# gl827.net
KiCad netlist of a schematic drawn in EAGLE
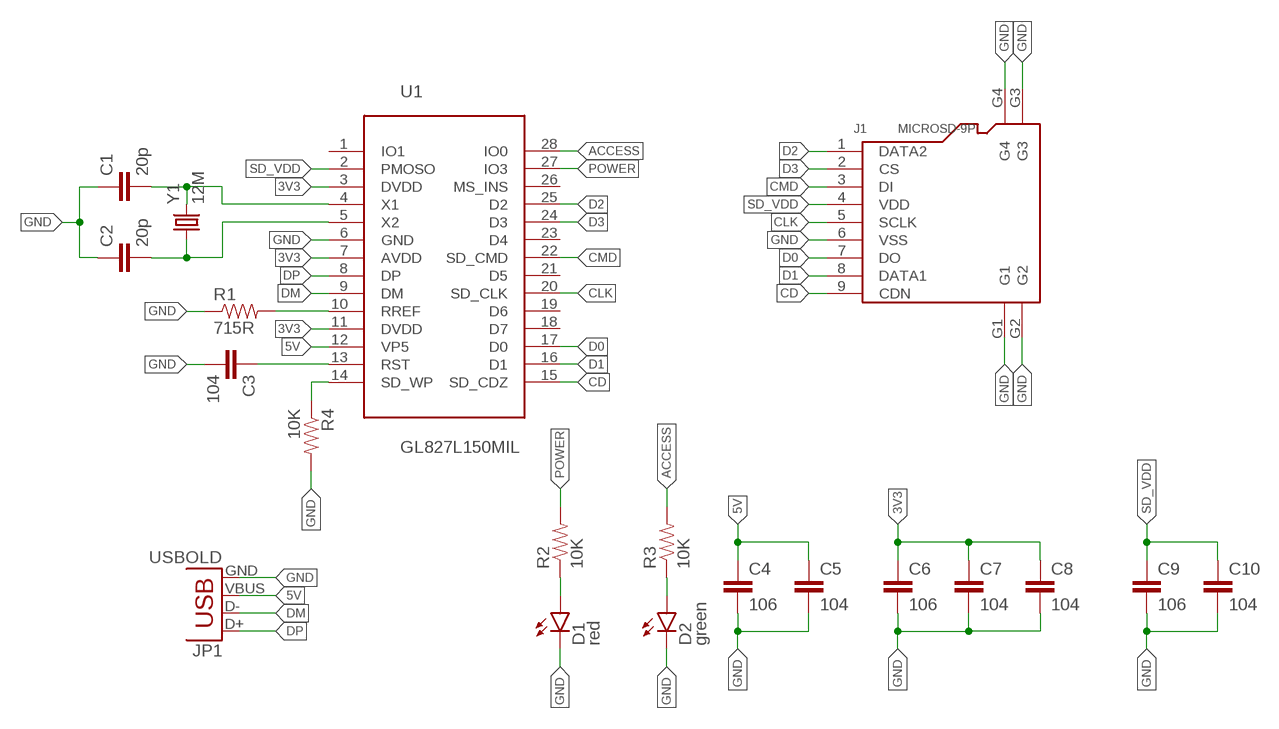
[diagram p0: schematic, sheet 1]

(export (version "E")
  (design (tool "Eeschema 10.0.6"))
  (components
    (comp (ref "C1")
      (value "20p")
      (footprint "eagle-import:0402-CAP")
      (libsource (lib "eagle-import") (part "CAP0402-CAP"))
    )
    (comp (ref "C2")
      (value "20p")
      (footprint "eagle-import:0402-CAP")
      (libsource (lib "eagle-import") (part "CAP0402-CAP"))
    )
    (comp (ref "C3")
      (value "104")
      (footprint "eagle-import:0402-CAP")
      (libsource (lib "eagle-import") (part "CAP0402-CAP"))
    )
    (comp (ref "C4")
      (value "106")
      (footprint "eagle-import:0402-CAP")
      (libsource (lib "eagle-import") (part "CAP0402-CAP"))
    )
    (comp (ref "C5")
      (value "104")
      (footprint "eagle-import:0402-CAP")
      (libsource (lib "eagle-import") (part "CAP0402-CAP"))
    )
    (comp (ref "C6")
      (value "106")
      (footprint "eagle-import:0402-CAP")
      (libsource (lib "eagle-import") (part "CAP0402-CAP"))
    )
    (comp (ref "C7")
      (value "104")
      (footprint "eagle-import:0402-CAP")
      (libsource (lib "eagle-import") (part "CAP0402-CAP"))
    )
    (comp (ref "C8")
      (value "104")
      (footprint "eagle-import:0402-CAP")
      (libsource (lib "eagle-import") (part "CAP0402-CAP"))
    )
    (comp (ref "C9")
      (value "106")
      (footprint "eagle-import:0402-CAP")
      (libsource (lib "eagle-import") (part "CAP0402-CAP"))
    )
    (comp (ref "C10")
      (value "104")
      (footprint "eagle-import:0402-CAP")
      (libsource (lib "eagle-import") (part "CAP0402-CAP"))
    )
    (comp (ref "D1")
      (value "red")
      (footprint "eagle-import:LED-0603-EASY")
      (libsource (lib "eagle-import") (part "LED-EASY"))
    )
    (comp (ref "D2")
      (value "green")
      (footprint "eagle-import:LED-0603-EASY")
      (libsource (lib "eagle-import") (part "LED-EASY"))
    )
    (comp (ref "J1")
      (value "MICROSD-9P")
      (footprint "eagle-import:MICRO-SD9+4P-SMD-16.1X14.5X1.85MM")
      (libsource (lib "eagle-import") (part "MICRO-SD-CARD-HOLDER-9P"))
    )
    (comp (ref "JP1")
      (value "USBOLD")
      (footprint "eagle-import:USB-MINIB-OLD")
      (libsource (lib "eagle-import") (part "USBOLD"))
    )
    (comp (ref "R1")
      (value "715R")
      (footprint "eagle-import:0603-RES")
      (libsource (lib "eagle-import") (part "RESISTOR0603"))
    )
    (comp (ref "R2")
      (value "10K")
      (footprint "eagle-import:0402-RES")
      (libsource (lib "eagle-import") (part "RESISTOR0402"))
    )
    (comp (ref "R3")
      (value "10K")
      (footprint "eagle-import:0402-RES")
      (libsource (lib "eagle-import") (part "RESISTOR0402"))
    )
    (comp (ref "R4")
      (value "10K")
      (footprint "eagle-import:0402-RES")
      (libsource (lib "eagle-import") (part "RESISTOR0402"))
    )
    (comp (ref "U1")
      (value "GL827L150MIL")
      (footprint "eagle-import:SSOP28-39")
      (libsource (lib "eagle-import") (part "GL827L150MIL"))
    )
    (comp (ref "Y1")
      (value "12M")
      (footprint "eagle-import:HC49US")
      (libsource (lib "eagle-import") (part "CRYSTAL2HC49US"))
    )
  )
  (nets
    (net (code "1") (name "3V3") (class "Default")
      (node (ref "C6") (pin "1") (pinfunction "1_1") (pintype "passive"))
      (node (ref "C7") (pin "1") (pinfunction "1_1") (pintype "passive"))
      (node (ref "C8") (pin "1") (pinfunction "1_1") (pintype "passive"))
      (node (ref "U1") (pin "11") (pinfunction "DVDD_11") (pintype "bidirectional"))
      (node (ref "U1") (pin "3") (pinfunction "DVDD_3") (pintype "bidirectional"))
      (node (ref "U1") (pin "7") (pinfunction "AVDD_7") (pintype "bidirectional"))
    )
    (net (code "2") (name "5V") (class "Default")
      (node (ref "C4") (pin "1") (pinfunction "1_1") (pintype "passive"))
      (node (ref "C5") (pin "1") (pinfunction "1_1") (pintype "passive"))
      (node (ref "JP1") (pin "VBUS") (pinfunction "VBUS_VBUS") (pintype "bidirectional"))
      (node (ref "U1") (pin "12") (pinfunction "VP5_12") (pintype "bidirectional"))
    )
    (net (code "3") (name "ACCESS") (class "Default")
      (node (ref "R3") (pin "2") (pinfunction "2_2") (pintype "passive"))
      (node (ref "U1") (pin "28") (pinfunction "IO0_28") (pintype "bidirectional"))
    )
    (net (code "4") (name "CD") (class "Default")
      (node (ref "J1") (pin "9") (pinfunction "CDN_9") (pintype "bidirectional"))
      (node (ref "U1") (pin "15") (pinfunction "SD_CDZ_15") (pintype "bidirectional"))
    )
    (net (code "5") (name "CLK") (class "Default")
      (node (ref "J1") (pin "5") (pinfunction "SCLK_5") (pintype "bidirectional"))
      (node (ref "U1") (pin "20") (pinfunction "SD_CLK_20") (pintype "bidirectional"))
    )
    (net (code "6") (name "CMD") (class "Default")
      (node (ref "J1") (pin "3") (pinfunction "DI_3") (pintype "bidirectional"))
      (node (ref "U1") (pin "22") (pinfunction "SD_CMD_22") (pintype "bidirectional"))
    )
    (net (code "7") (name "D0") (class "Default")
      (node (ref "J1") (pin "7") (pinfunction "DO_7") (pintype "bidirectional"))
      (node (ref "U1") (pin "17") (pinfunction "D0_17") (pintype "bidirectional"))
    )
    (net (code "8") (name "D1") (class "Default")
      (node (ref "J1") (pin "8") (pinfunction "DATA1_8") (pintype "bidirectional"))
      (node (ref "U1") (pin "16") (pinfunction "D1_16") (pintype "bidirectional"))
    )
    (net (code "9") (name "D2") (class "Default")
      (node (ref "J1") (pin "1") (pinfunction "DATA2_1") (pintype "bidirectional"))
      (node (ref "U1") (pin "25") (pinfunction "D2_25") (pintype "bidirectional"))
    )
    (net (code "10") (name "D3") (class "Default")
      (node (ref "J1") (pin "2") (pinfunction "CS_2") (pintype "bidirectional"))
      (node (ref "U1") (pin "24") (pinfunction "D3_24") (pintype "bidirectional"))
    )
    (net (code "11") (name "DM") (class "Default")
      (node (ref "JP1") (pin "D-") (pinfunction "D-_D-") (pintype "bidirectional"))
      (node (ref "U1") (pin "9") (pinfunction "DM_9") (pintype "bidirectional"))
    )
    (net (code "12") (name "DP") (class "Default")
      (node (ref "JP1") (pin "D+") (pinfunction "D+_D+") (pintype "bidirectional"))
      (node (ref "U1") (pin "8") (pinfunction "DP_8") (pintype "bidirectional"))
    )
    (net (code "13") (name "GND") (class "Default")
      (node (ref "C1") (pin "1") (pinfunction "1_1") (pintype "passive"))
      (node (ref "C10") (pin "2") (pinfunction "2_2") (pintype "passive"))
      (node (ref "C2") (pin "1") (pinfunction "1_1") (pintype "passive"))
      (node (ref "C3") (pin "2") (pinfunction "2_2") (pintype "passive"))
      (node (ref "C4") (pin "2") (pinfunction "2_2") (pintype "passive"))
      (node (ref "C5") (pin "2") (pinfunction "2_2") (pintype "passive"))
      (node (ref "C6") (pin "2") (pinfunction "2_2") (pintype "passive"))
      (node (ref "C7") (pin "2") (pinfunction "2_2") (pintype "passive"))
      (node (ref "C8") (pin "2") (pinfunction "2_2") (pintype "passive"))
      (node (ref "C9") (pin "2") (pinfunction "2_2") (pintype "passive"))
      (node (ref "D1") (pin "-") (pinfunction "C_-") (pintype "passive"))
      (node (ref "D2") (pin "-") (pinfunction "C_-") (pintype "passive"))
      (node (ref "J1") (pin "6") (pinfunction "VSS_6") (pintype "bidirectional"))
      (node (ref "J1") (pin "G1") (pinfunction "G1_G1") (pintype "bidirectional"))
      (node (ref "J1") (pin "G2") (pinfunction "G2_G2") (pintype "bidirectional"))
      (node (ref "J1") (pin "G3") (pinfunction "G3_G3") (pintype "bidirectional"))
      (node (ref "J1") (pin "G4") (pinfunction "G4_G4") (pintype "bidirectional"))
      (node (ref "JP1") (pin "GND") (pinfunction "GND_GND") (pintype "bidirectional"))
      (node (ref "R1") (pin "1") (pinfunction "1_1") (pintype "passive"))
      (node (ref "R4") (pin "2") (pinfunction "2_2") (pintype "passive"))
      (node (ref "U1") (pin "6") (pinfunction "GND_6") (pintype "bidirectional"))
    )
    (net (code "14") (name "Net-(D1-A)") (class "Default")
      (node (ref "D1") (pin "+") (pinfunction "A_+") (pintype "passive"))
      (node (ref "R2") (pin "1") (pinfunction "1_1") (pintype "passive"))
    )
    (net (code "15") (name "Net-(D2-A)") (class "Default")
      (node (ref "D2") (pin "+") (pinfunction "A_+") (pintype "passive"))
      (node (ref "R3") (pin "1") (pinfunction "1_1") (pintype "passive"))
    )
    (net (code "16") (name "Net-(U1-RREF)") (class "Default")
      (node (ref "R1") (pin "2") (pinfunction "2_2") (pintype "passive"))
      (node (ref "U1") (pin "10") (pinfunction "RREF_10") (pintype "bidirectional"))
    )
    (net (code "17") (name "Net-(U1-RST)") (class "Default")
      (node (ref "C3") (pin "1") (pinfunction "1_1") (pintype "passive"))
      (node (ref "U1") (pin "13") (pinfunction "RST_13") (pintype "bidirectional"))
    )
    (net (code "18") (name "Net-(U1-SD_WP)") (class "Default")
      (node (ref "R4") (pin "1") (pinfunction "1_1") (pintype "passive"))
      (node (ref "U1") (pin "14") (pinfunction "SD_WP_14") (pintype "bidirectional"))
    )
    (net (code "19") (name "Net-(U1-X1)") (class "Default")
      (node (ref "C1") (pin "2") (pinfunction "2_2") (pintype "passive"))
      (node (ref "U1") (pin "4") (pinfunction "X1_4") (pintype "bidirectional"))
      (node (ref "Y1") (pin "2") (pinfunction "2_2") (pintype "passive"))
    )
    (net (code "20") (name "Net-(U1-X2)") (class "Default")
      (node (ref "C2") (pin "2") (pinfunction "2_2") (pintype "passive"))
      (node (ref "U1") (pin "5") (pinfunction "X2_5") (pintype "bidirectional"))
      (node (ref "Y1") (pin "1") (pinfunction "1_1") (pintype "passive"))
    )
    (net (code "21") (name "POWER") (class "Default")
      (node (ref "R2") (pin "2") (pinfunction "2_2") (pintype "passive"))
      (node (ref "U1") (pin "27") (pinfunction "IO3_27") (pintype "bidirectional"))
    )
    (net (code "22") (name "SD_VDD") (class "Default")
      (node (ref "C10") (pin "1") (pinfunction "1_1") (pintype "passive"))
      (node (ref "C9") (pin "1") (pinfunction "1_1") (pintype "passive"))
      (node (ref "J1") (pin "4") (pinfunction "VDD_4") (pintype "bidirectional"))
      (node (ref "U1") (pin "2") (pinfunction "PMOSO_2") (pintype "bidirectional"))
    )
    (net (code "23") (name "unconnected-(U1-D4-Pad23)") (class "Default")
      (node (ref "U1") (pin "23") (pinfunction "D4_23") (pintype "bidirectional"))
    )
    (net (code "24") (name "unconnected-(U1-D5-Pad21)") (class "Default")
      (node (ref "U1") (pin "21") (pinfunction "D5_21") (pintype "bidirectional"))
    )
    (net (code "25") (name "unconnected-(U1-D6-Pad19)") (class "Default")
      (node (ref "U1") (pin "19") (pinfunction "D6_19") (pintype "bidirectional"))
    )
    (net (code "26") (name "unconnected-(U1-D7-Pad18)") (class "Default")
      (node (ref "U1") (pin "18") (pinfunction "D7_18") (pintype "bidirectional"))
    )
    (net (code "27") (name "unconnected-(U1-IO1-Pad1)") (class "Default")
      (node (ref "U1") (pin "1") (pinfunction "IO1_1") (pintype "bidirectional"))
    )
    (net (code "28") (name "unconnected-(U1-MS_INS-Pad26)") (class "Default")
      (node (ref "U1") (pin "26") (pinfunction "MS_INS_26") (pintype "bidirectional"))
    )
  )
)
